# io-pack-2-1.net
KiCad netlist of a schematic drawn in EAGLE
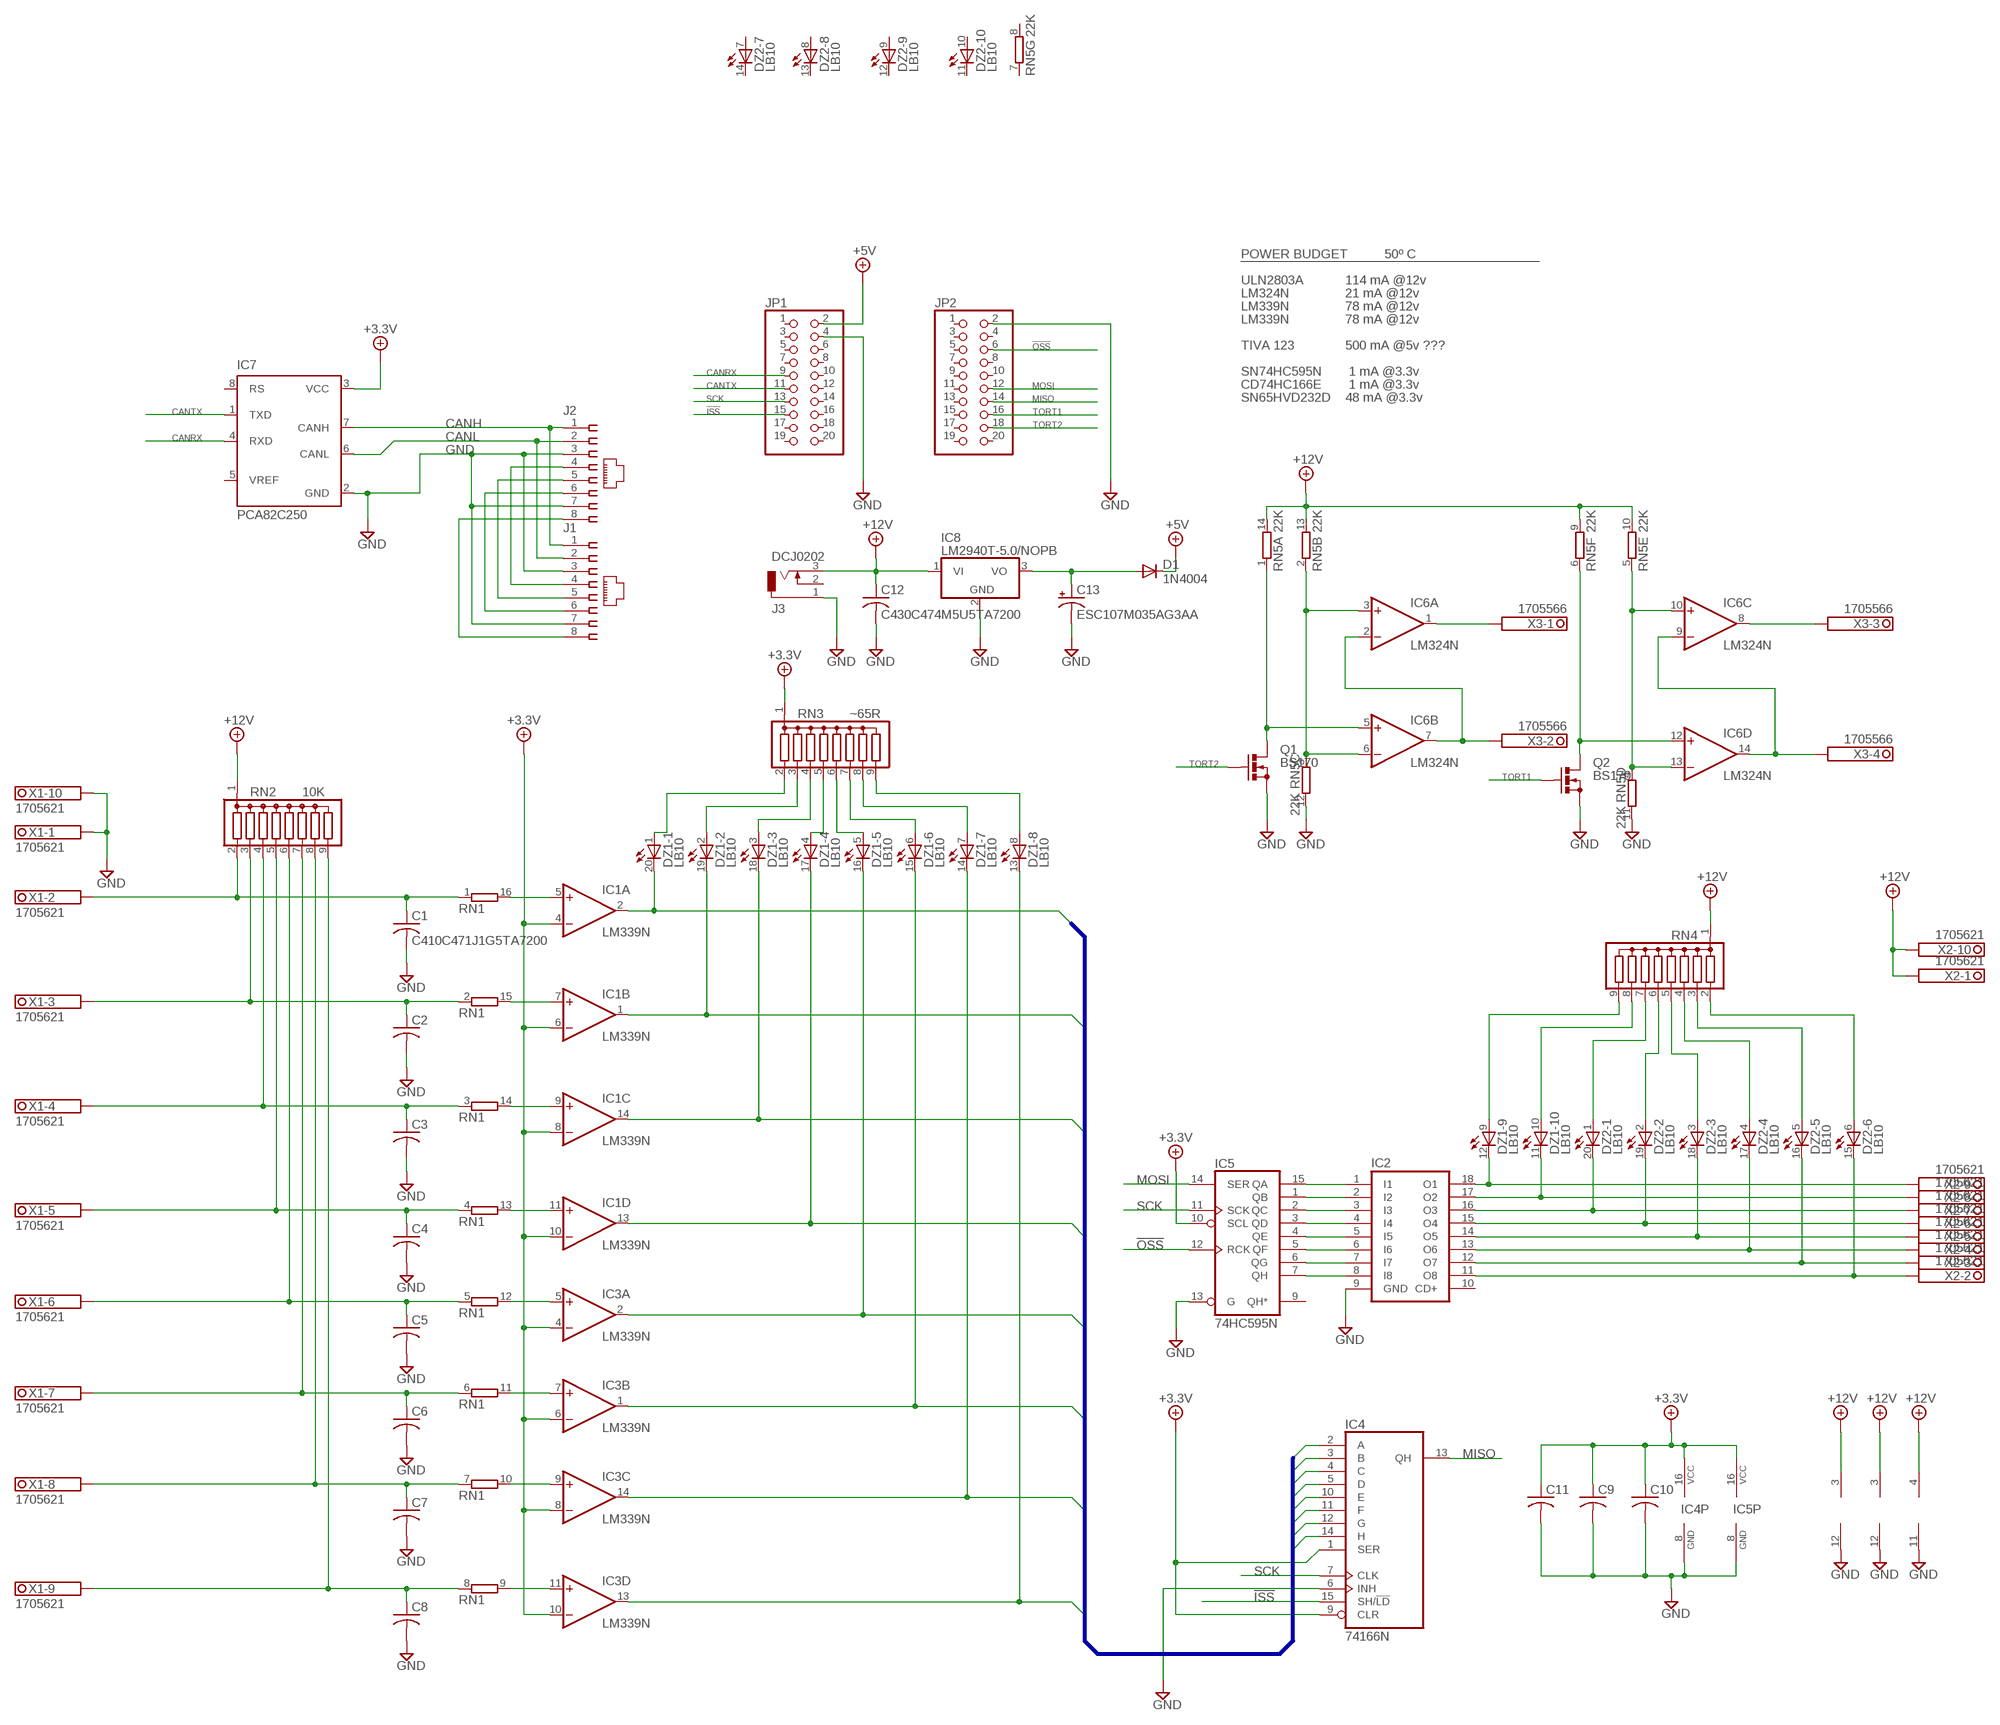
[diagram p0: schematic, sheet 1]

(export (version "E")
  (design (tool "Eeschema 10.0.6"))
  (components
    (comp (ref "C1")
      (value "C410C471J1G5TA7200")
      (footprint "eagle-import:C050-025X075")
      (libsource (lib "eagle-import") (part "C-US050-025X075"))
    )
    (comp (ref "C2")
      (value "C-US050-025X075")
      (footprint "eagle-import:C050-025X075")
      (libsource (lib "eagle-import") (part "C-US050-025X075"))
    )
    (comp (ref "C3")
      (value "C-US050-025X075")
      (footprint "eagle-import:C050-025X075")
      (libsource (lib "eagle-import") (part "C-US050-025X075"))
    )
    (comp (ref "C4")
      (value "C-US050-025X075")
      (footprint "eagle-import:C050-025X075")
      (libsource (lib "eagle-import") (part "C-US050-025X075"))
    )
    (comp (ref "C5")
      (value "C-US050-025X075")
      (footprint "eagle-import:C050-025X075")
      (libsource (lib "eagle-import") (part "C-US050-025X075"))
    )
    (comp (ref "C6")
      (value "C-US050-025X075")
      (footprint "eagle-import:C050-025X075")
      (libsource (lib "eagle-import") (part "C-US050-025X075"))
    )
    (comp (ref "C7")
      (value "C-US050-025X075")
      (footprint "eagle-import:C050-025X075")
      (libsource (lib "eagle-import") (part "C-US050-025X075"))
    )
    (comp (ref "C8")
      (value "C-US050-025X075")
      (footprint "eagle-import:C050-025X075")
      (libsource (lib "eagle-import") (part "C-US050-025X075"))
    )
    (comp (ref "C9")
      (value "C-US050-025X075")
      (footprint "eagle-import:C050-025X075")
      (libsource (lib "eagle-import") (part "C-US050-025X075"))
    )
    (comp (ref "C10")
      (value "C-US050-025X075")
      (footprint "eagle-import:C050-025X075")
      (libsource (lib "eagle-import") (part "C-US050-025X075"))
    )
    (comp (ref "C11")
      (value "C-US050-025X075")
      (footprint "eagle-import:C050-025X075")
      (libsource (lib "eagle-import") (part "C-US050-025X075"))
    )
    (comp (ref "C12")
      (value "C430C474M5U5TA7200")
      (footprint "eagle-import:C075-032X103")
      (libsource (lib "eagle-import") (part "C-US075-032X103"))
    )
    (comp (ref "C13")
      (value "ESC107M035AG3AA")
      (footprint "eagle-import:E3,5-8")
      (libsource (lib "eagle-import") (part "CPOL-USE3.5-8"))
    )
    (comp (ref "D1")
      (value "1N4004")
      (footprint "eagle-import:DO41-10")
      (libsource (lib "eagle-import") (part "1N4004"))
    )
    (comp (ref "DZ1")
      (value "LB10")
      (footprint "eagle-import:LB10")
      (libsource (lib "eagle-import") (part "LB10"))
    )
    (comp (ref "DZ2")
      (value "LB10")
      (footprint "eagle-import:LB10")
      (libsource (lib "eagle-import") (part "LB10"))
    )
    (comp (ref "IC1")
      (value "LM339N")
      (footprint "eagle-import:DIL14")
      (libsource (lib "eagle-import") (part "LM339N"))
    )
    (comp (ref "IC2")
      (value "ULN2803A")
      (footprint "eagle-import:DIL18")
      (libsource (lib "eagle-import") (part "ULN2803A"))
    )
    (comp (ref "IC3")
      (value "LM339N")
      (footprint "eagle-import:DIL14")
      (libsource (lib "eagle-import") (part "LM339N"))
    )
    (comp (ref "IC4")
      (value "74166N")
      (footprint "eagle-import:DIL16")
      (libsource (lib "eagle-import") (part "74166N"))
    )
    (comp (ref "IC5")
      (value "74HC595N")
      (footprint "eagle-import:DIL16")
      (libsource (lib "eagle-import") (part "74595NLS"))
    )
    (comp (ref "IC6")
      (value "LM324N")
      (footprint "eagle-import:DIL14")
      (libsource (lib "eagle-import") (part "LM324N"))
    )
    (comp (ref "IC7")
      (value "PCA82C250")
      (footprint "eagle-import:DIL08")
      (libsource (lib "eagle-import") (part "PCA82C250"))
    )
    (comp (ref "IC8")
      (value "LM2940T-5.0/NOPB")
      (footprint "eagle-import:TO220V")
      (libsource (lib "eagle-import") (part "78TV05"))
    )
    (comp (ref "J1")
      (value "555164-1")
      (footprint "eagle-import:555164-1")
      (libsource (lib "eagle-import") (part "555164-1"))
    )
    (comp (ref "J2")
      (value "555164-1")
      (footprint "eagle-import:555164-1")
      (libsource (lib "eagle-import") (part "555164-1"))
    )
    (comp (ref "J3")
      (value "DCJ0202")
      (footprint "eagle-import:DCJ0202")
      (libsource (lib "eagle-import") (part "DCJ0202"))
    )
    (comp (ref "JP1")
      (value "PINHD-2X10")
      (footprint "eagle-import:2X10")
      (libsource (lib "eagle-import") (part "PINHD-2X10"))
    )
    (comp (ref "JP2")
      (value "PINHD-2X10")
      (footprint "eagle-import:2X10")
      (libsource (lib "eagle-import") (part "PINHD-2X10"))
    )
    (comp (ref "Q1")
      (value "BS170")
      (footprint "eagle-import:SOT54E")
      (libsource (lib "eagle-import") (part "BS170"))
    )
    (comp (ref "Q2")
      (value "BS170")
      (footprint "eagle-import:SOT54E")
      (libsource (lib "eagle-import") (part "BS170"))
    )
    (comp (ref "RN1")
      (value "8R-P")
      (footprint "eagle-import:DIL16")
      (libsource (lib "eagle-import") (part "8R-P"))
    )
    (comp (ref "RN2")
      (value "10K")
      (footprint "eagle-import:SIL9")
      (libsource (lib "eagle-import") (part "G08R"))
    )
    (comp (ref "RN3")
      (value "~65R")
      (footprint "eagle-import:SIL9")
      (libsource (lib "eagle-import") (part "G08R"))
    )
    (comp (ref "RN4")
      (value "G08R")
      (footprint "eagle-import:SIL9")
      (libsource (lib "eagle-import") (part "G08R"))
    )
    (comp (ref "RN5")
      (value "22K")
      (footprint "eagle-import:DIL14")
      (libsource (lib "eagle-import") (part "7R-N"))
    )
    (comp (ref "X1")
      (value "1705621")
      (footprint "eagle-import:1705621")
      (libsource (lib "eagle-import") (part "1705621"))
    )
    (comp (ref "X2")
      (value "1705621")
      (footprint "eagle-import:1705621")
      (libsource (lib "eagle-import") (part "1705621"))
    )
    (comp (ref "X3")
      (value "1705566")
      (footprint "eagle-import:1705566")
      (libsource (lib "eagle-import") (part "1705566"))
    )
  )
  (nets
    (net (code "1") (name "+3.3V") (class "Default")
      (node (ref "C10") (pin "1") (pinfunction "1_1") (pintype "passive"))
      (node (ref "C11") (pin "1") (pinfunction "1_1") (pintype "passive"))
      (node (ref "C9") (pin "1") (pinfunction "1_1") (pintype "passive"))
      (node (ref "IC1") (pin "10") (pinfunction "-IN_10") (pintype "input"))
      (node (ref "IC1") (pin "4") (pinfunction "-IN_4") (pintype "input"))
      (node (ref "IC1") (pin "6") (pinfunction "-IN_6") (pintype "input"))
      (node (ref "IC1") (pin "8") (pinfunction "-IN_8") (pintype "input"))
      (node (ref "IC3") (pin "10") (pinfunction "-IN_10") (pintype "input"))
      (node (ref "IC3") (pin "4") (pinfunction "-IN_4") (pintype "input"))
      (node (ref "IC3") (pin "6") (pinfunction "-IN_6") (pintype "input"))
      (node (ref "IC3") (pin "8") (pinfunction "-IN_8") (pintype "input"))
      (node (ref "IC4") (pin "1") (pinfunction "SER_1") (pintype "input"))
      (node (ref "IC4") (pin "16") (pinfunction "VCC_16") (pintype "power_in"))
      (node (ref "IC4") (pin "9") (pinfunction "CLR_9") (pintype "input"))
      (node (ref "IC5") (pin "10") (pinfunction "SCL_10") (pintype "input"))
      (node (ref "IC5") (pin "16") (pinfunction "VCC_16") (pintype "power_in"))
      (node (ref "IC7") (pin "3") (pinfunction "VCC_3") (pintype "power_in"))
      (node (ref "RN3") (pin "1") (pinfunction "1_1") (pintype "passive"))
    )
    (net (code "2") (name "+5V") (class "Default")
      (node (ref "D1") (pin "C") (pinfunction "C_C") (pintype "passive"))
      (node (ref "JP1") (pin "2") (pinfunction "2_2") (pintype "passive"))
    )
    (net (code "3") (name "+12V") (class "Default")
      (node (ref "C12") (pin "1") (pinfunction "1_1") (pintype "passive"))
      (node (ref "IC1") (pin "3") (pinfunction "V+_3") (pintype "power_in"))
      (node (ref "IC3") (pin "3") (pinfunction "V+_3") (pintype "power_in"))
      (node (ref "IC6") (pin "4") (pinfunction "V+_4") (pintype "power_in"))
      (node (ref "IC8") (pin "1") (pinfunction "VI_1") (pintype "input"))
      (node (ref "J3") (pin "3") (pinfunction "3_3") (pintype "passive"))
      (node (ref "RN2") (pin "1") (pinfunction "1_1") (pintype "passive"))
      (node (ref "RN4") (pin "1") (pinfunction "1_1") (pintype "passive"))
      (node (ref "RN5") (pin "10") (pinfunction "2_10") (pintype "passive"))
      (node (ref "RN5") (pin "13") (pinfunction "2_13") (pintype "passive"))
      (node (ref "RN5") (pin "14") (pinfunction "2_14") (pintype "passive"))
      (node (ref "RN5") (pin "9") (pinfunction "2_9") (pintype "passive"))
      (node (ref "X2") (pin "1.1") (pinfunction "1A_1.1") (pintype "passive"))
      (node (ref "X2") (pin "1.2") (pinfunction "1A_1.2") (pintype "passive"))
      (node (ref "X2") (pin "10.1") (pinfunction "1A_10.1") (pintype "passive"))
      (node (ref "X2") (pin "10.2") (pinfunction "1A_10.2") (pintype "passive"))
    )
    (net (code "4") (name "/CANH") (class "Default")
      (node (ref "IC7") (pin "7") (pinfunction "CANH_7") (pintype "bidirectional"))
      (node (ref "J1") (pin "1") (pinfunction "1_1") (pintype "passive"))
      (node (ref "J2") (pin "1") (pinfunction "1_1") (pintype "passive"))
    )
    (net (code "5") (name "/CANL") (class "Default")
      (node (ref "IC7") (pin "6") (pinfunction "CANL_6") (pintype "bidirectional"))
      (node (ref "J1") (pin "2") (pinfunction "2_2") (pintype "passive"))
      (node (ref "J2") (pin "2") (pinfunction "2_2") (pintype "passive"))
    )
    (net (code "6") (name "/CANRX") (class "Default")
      (node (ref "IC7") (pin "4") (pinfunction "RXD_4") (pintype "output"))
      (node (ref "JP1") (pin "9") (pinfunction "9_9") (pintype "passive"))
    )
    (net (code "7") (name "/CANTX") (class "Default")
      (node (ref "IC7") (pin "1") (pinfunction "TXD_1") (pintype "input"))
      (node (ref "JP1") (pin "11") (pinfunction "11_11") (pintype "passive"))
    )
    (net (code "8") (name "/IN0") (class "Default")
      (node (ref "DZ1") (pin "20") (pinfunction "C_20") (pintype "passive"))
      (node (ref "IC1") (pin "2") (pinfunction "OUT_2") (pintype "open_collector"))
      (node (ref "IC4") (pin "2") (pinfunction "A_2") (pintype "input"))
    )
    (net (code "9") (name "/IN1") (class "Default")
      (node (ref "DZ1") (pin "19") (pinfunction "C_19") (pintype "passive"))
      (node (ref "IC1") (pin "1") (pinfunction "OUT_1") (pintype "open_collector"))
      (node (ref "IC4") (pin "3") (pinfunction "B_3") (pintype "input"))
    )
    (net (code "10") (name "/IN2") (class "Default")
      (node (ref "DZ1") (pin "18") (pinfunction "C_18") (pintype "passive"))
      (node (ref "IC1") (pin "14") (pinfunction "OUT_14") (pintype "open_collector"))
      (node (ref "IC4") (pin "4") (pinfunction "C_4") (pintype "input"))
    )
    (net (code "11") (name "/IN3") (class "Default")
      (node (ref "DZ1") (pin "17") (pinfunction "C_17") (pintype "passive"))
      (node (ref "IC1") (pin "13") (pinfunction "OUT_13") (pintype "open_collector"))
      (node (ref "IC4") (pin "5") (pinfunction "D_5") (pintype "input"))
    )
    (net (code "12") (name "/IN4") (class "Default")
      (node (ref "DZ1") (pin "16") (pinfunction "C_16") (pintype "passive"))
      (node (ref "IC3") (pin "2") (pinfunction "OUT_2") (pintype "open_collector"))
      (node (ref "IC4") (pin "10") (pinfunction "E_10") (pintype "input"))
    )
    (net (code "13") (name "/IN5") (class "Default")
      (node (ref "DZ1") (pin "15") (pinfunction "C_15") (pintype "passive"))
      (node (ref "IC3") (pin "1") (pinfunction "OUT_1") (pintype "open_collector"))
      (node (ref "IC4") (pin "11") (pinfunction "F_11") (pintype "input"))
    )
    (net (code "14") (name "/IN6") (class "Default")
      (node (ref "DZ1") (pin "14") (pinfunction "C_14") (pintype "passive"))
      (node (ref "IC3") (pin "14") (pinfunction "OUT_14") (pintype "open_collector"))
      (node (ref "IC4") (pin "12") (pinfunction "G_12") (pintype "input"))
    )
    (net (code "15") (name "/IN7") (class "Default")
      (node (ref "DZ1") (pin "13") (pinfunction "C_13") (pintype "passive"))
      (node (ref "IC3") (pin "13") (pinfunction "OUT_13") (pintype "open_collector"))
      (node (ref "IC4") (pin "14") (pinfunction "H_14") (pintype "input"))
    )
    (net (code "16") (name "/MISO") (class "Default")
      (node (ref "IC4") (pin "13") (pinfunction "QH_13") (pintype "output"))
      (node (ref "JP2") (pin "14") (pinfunction "14_14") (pintype "passive"))
    )
    (net (code "17") (name "/MOSI") (class "Default")
      (node (ref "IC5") (pin "14") (pinfunction "SER_14") (pintype "input"))
      (node (ref "JP2") (pin "12") (pinfunction "12_12") (pintype "passive"))
    )
    (net (code "18") (name "/SCK") (class "Default")
      (node (ref "IC4") (pin "7") (pinfunction "CLK_7") (pintype "input"))
      (node (ref "IC5") (pin "11") (pinfunction "SCK_11") (pintype "input"))
      (node (ref "JP1") (pin "13") (pinfunction "13_13") (pintype "passive"))
    )
    (net (code "19") (name "/TORT1") (class "Default")
      (node (ref "JP2") (pin "16") (pinfunction "16_16") (pintype "passive"))
      (node (ref "Q2") (pin "G") (pinfunction "G_G") (pintype "passive"))
    )
    (net (code "20") (name "/TORT2") (class "Default")
      (node (ref "JP2") (pin "18") (pinfunction "18_18") (pintype "passive"))
      (node (ref "Q1") (pin "G") (pinfunction "G_G") (pintype "passive"))
    )
    (net (code "21") (name "/~{ISS}") (class "Default")
      (node (ref "IC4") (pin "15") (pinfunction "SH/~{LD}_15") (pintype "input"))
      (node (ref "JP1") (pin "15") (pinfunction "15_15") (pintype "passive"))
    )
    (net (code "22") (name "/~{OSS}") (class "Default")
      (node (ref "IC5") (pin "12") (pinfunction "RCK_12") (pintype "input"))
      (node (ref "JP2") (pin "6") (pinfunction "6_6") (pintype "passive"))
    )
    (net (code "23") (name "GND") (class "Default")
      (node (ref "C1") (pin "2") (pinfunction "2_2") (pintype "passive"))
      (node (ref "C10") (pin "2") (pinfunction "2_2") (pintype "passive"))
      (node (ref "C11") (pin "2") (pinfunction "2_2") (pintype "passive"))
      (node (ref "C12") (pin "2") (pinfunction "2_2") (pintype "passive"))
      (node (ref "C13") (pin "-") (pinfunction "-_-") (pintype "passive"))
      (node (ref "C2") (pin "2") (pinfunction "2_2") (pintype "passive"))
      (node (ref "C3") (pin "2") (pinfunction "2_2") (pintype "passive"))
      (node (ref "C4") (pin "2") (pinfunction "2_2") (pintype "passive"))
      (node (ref "C5") (pin "2") (pinfunction "2_2") (pintype "passive"))
      (node (ref "C6") (pin "2") (pinfunction "2_2") (pintype "passive"))
      (node (ref "C7") (pin "2") (pinfunction "2_2") (pintype "passive"))
      (node (ref "C8") (pin "2") (pinfunction "2_2") (pintype "passive"))
      (node (ref "C9") (pin "2") (pinfunction "2_2") (pintype "passive"))
      (node (ref "IC1") (pin "12") (pinfunction "GND_12") (pintype "power_in"))
      (node (ref "IC2") (pin "9") (pinfunction "GND_9") (pintype "power_in"))
      (node (ref "IC3") (pin "12") (pinfunction "GND_12") (pintype "power_in"))
      (node (ref "IC4") (pin "6") (pinfunction "INH_6") (pintype "input"))
      (node (ref "IC4") (pin "8") (pinfunction "GND_8") (pintype "power_in"))
      (node (ref "IC5") (pin "13") (pinfunction "G_13") (pintype "input"))
      (node (ref "IC5") (pin "8") (pinfunction "GND_8") (pintype "power_in"))
      (node (ref "IC6") (pin "11") (pinfunction "V-_11") (pintype "power_in"))
      (node (ref "IC7") (pin "2") (pinfunction "GND_2") (pintype "power_in"))
      (node (ref "IC8") (pin "2") (pinfunction "GND_2") (pintype "passive"))
      (node (ref "J1") (pin "3") (pinfunction "3_3") (pintype "passive"))
      (node (ref "J1") (pin "7") (pinfunction "7_7") (pintype "passive"))
      (node (ref "J2") (pin "3") (pinfunction "3_3") (pintype "passive"))
      (node (ref "J2") (pin "7") (pinfunction "7_7") (pintype "passive"))
      (node (ref "J3") (pin "1") (pinfunction "1_1") (pintype "passive"))
      (node (ref "JP1") (pin "4") (pinfunction "4_4") (pintype "passive"))
      (node (ref "JP2") (pin "2") (pinfunction "2_2") (pintype "passive"))
      (node (ref "Q1") (pin "S") (pinfunction "S_S") (pintype "passive"))
      (node (ref "Q2") (pin "S") (pinfunction "S_S") (pintype "passive"))
      (node (ref "RN5") (pin "11") (pinfunction "2_11") (pintype "passive"))
      (node (ref "RN5") (pin "12") (pinfunction "2_12") (pintype "passive"))
      (node (ref "X1") (pin "1.1") (pinfunction "1A_1.1") (pintype "passive"))
      (node (ref "X1") (pin "1.2") (pinfunction "1A_1.2") (pintype "passive"))
      (node (ref "X1") (pin "10.1") (pinfunction "1A_10.1") (pintype "passive"))
      (node (ref "X1") (pin "10.2") (pinfunction "1A_10.2") (pintype "passive"))
    )
    (net (code "24") (name "Net-(C1-Pad1)") (class "Default")
      (node (ref "C1") (pin "1") (pinfunction "1_1") (pintype "passive"))
      (node (ref "RN1") (pin "1") (pinfunction "1_1") (pintype "passive"))
      (node (ref "RN2") (pin "2") (pinfunction "2_2") (pintype "passive"))
      (node (ref "X1") (pin "2.1") (pinfunction "1A_2.1") (pintype "passive"))
      (node (ref "X1") (pin "2.2") (pinfunction "1A_2.2") (pintype "passive"))
    )
    (net (code "25") (name "Net-(DZ1A-A)") (class "Default")
      (node (ref "DZ1") (pin "1") (pinfunction "A_1") (pintype "passive"))
      (node (ref "RN3") (pin "2") (pinfunction "2_2") (pintype "passive"))
    )
    (net (code "26") (name "Net-(DZ1B-A)") (class "Default")
      (node (ref "DZ1") (pin "10") (pinfunction "A_10") (pintype "passive"))
      (node (ref "RN4") (pin "8") (pinfunction "8_8") (pintype "passive"))
    )
    (net (code "27") (name "Net-(DZ1B-C)") (class "Default")
      (node (ref "DZ1") (pin "11") (pinfunction "C_11") (pintype "passive"))
      (node (ref "IC2") (pin "17") (pinfunction "O2_17") (pintype "open_collector"))
      (node (ref "X2") (pin "8.1") (pinfunction "1A_8.1") (pintype "passive"))
      (node (ref "X2") (pin "8.2") (pinfunction "1A_8.2") (pintype "passive"))
    )
    (net (code "28") (name "Net-(DZ1C-A)") (class "Default")
      (node (ref "DZ1") (pin "2") (pinfunction "A_2") (pintype "passive"))
      (node (ref "RN3") (pin "3") (pinfunction "3_3") (pintype "passive"))
    )
    (net (code "29") (name "Net-(DZ1D-A)") (class "Default")
      (node (ref "DZ1") (pin "3") (pinfunction "A_3") (pintype "passive"))
      (node (ref "RN3") (pin "4") (pinfunction "4_4") (pintype "passive"))
    )
    (net (code "30") (name "Net-(DZ1E-A)") (class "Default")
      (node (ref "DZ1") (pin "4") (pinfunction "A_4") (pintype "passive"))
      (node (ref "RN3") (pin "5") (pinfunction "5_5") (pintype "passive"))
    )
    (net (code "31") (name "Net-(DZ1F-A)") (class "Default")
      (node (ref "DZ1") (pin "5") (pinfunction "A_5") (pintype "passive"))
      (node (ref "RN3") (pin "6") (pinfunction "6_6") (pintype "passive"))
    )
    (net (code "32") (name "Net-(DZ1G-A)") (class "Default")
      (node (ref "DZ1") (pin "6") (pinfunction "A_6") (pintype "passive"))
      (node (ref "RN3") (pin "7") (pinfunction "7_7") (pintype "passive"))
    )
    (net (code "33") (name "Net-(DZ1H-A)") (class "Default")
      (node (ref "DZ1") (pin "7") (pinfunction "A_7") (pintype "passive"))
      (node (ref "RN3") (pin "8") (pinfunction "8_8") (pintype "passive"))
    )
    (net (code "34") (name "Net-(DZ1I-A)") (class "Default")
      (node (ref "DZ1") (pin "8") (pinfunction "A_8") (pintype "passive"))
      (node (ref "RN3") (pin "9") (pinfunction "9_9") (pintype "passive"))
    )
    (net (code "35") (name "Net-(DZ1J-A)") (class "Default")
      (node (ref "DZ1") (pin "9") (pinfunction "A_9") (pintype "passive"))
      (node (ref "RN4") (pin "9") (pinfunction "9_9") (pintype "passive"))
    )
    (net (code "36") (name "Net-(DZ1J-C)") (class "Default")
      (node (ref "DZ1") (pin "12") (pinfunction "C_12") (pintype "passive"))
      (node (ref "IC2") (pin "18") (pinfunction "O1_18") (pintype "open_collector"))
      (node (ref "X2") (pin "9.1") (pinfunction "1A_9.1") (pintype "passive"))
      (node (ref "X2") (pin "9.2") (pinfunction "1A_9.2") (pintype "passive"))
    )
    (net (code "37") (name "Net-(DZ2A-A)") (class "Default")
      (node (ref "DZ2") (pin "1") (pinfunction "A_1") (pintype "passive"))
      (node (ref "RN4") (pin "7") (pinfunction "7_7") (pintype "passive"))
    )
    (net (code "38") (name "Net-(DZ2A-C)") (class "Default")
      (node (ref "DZ2") (pin "20") (pinfunction "C_20") (pintype "passive"))
      (node (ref "IC2") (pin "16") (pinfunction "O3_16") (pintype "open_collector"))
      (node (ref "X2") (pin "7.1") (pinfunction "1A_7.1") (pintype "passive"))
      (node (ref "X2") (pin "7.2") (pinfunction "1A_7.2") (pintype "passive"))
    )
    (net (code "39") (name "Net-(DZ2C-A)") (class "Default")
      (node (ref "DZ2") (pin "2") (pinfunction "A_2") (pintype "passive"))
      (node (ref "RN4") (pin "6") (pinfunction "6_6") (pintype "passive"))
    )
    (net (code "40") (name "Net-(DZ2C-C)") (class "Default")
      (node (ref "DZ2") (pin "19") (pinfunction "C_19") (pintype "passive"))
      (node (ref "IC2") (pin "15") (pinfunction "O4_15") (pintype "open_collector"))
      (node (ref "X2") (pin "6.1") (pinfunction "1A_6.1") (pintype "passive"))
      (node (ref "X2") (pin "6.2") (pinfunction "1A_6.2") (pintype "passive"))
    )
    (net (code "41") (name "Net-(DZ2D-A)") (class "Default")
      (node (ref "DZ2") (pin "3") (pinfunction "A_3") (pintype "passive"))
      (node (ref "RN4") (pin "5") (pinfunction "5_5") (pintype "passive"))
    )
    (net (code "42") (name "Net-(DZ2D-C)") (class "Default")
      (node (ref "DZ2") (pin "18") (pinfunction "C_18") (pintype "passive"))
      (node (ref "IC2") (pin "14") (pinfunction "O5_14") (pintype "open_collector"))
      (node (ref "X2") (pin "5.1") (pinfunction "1A_5.1") (pintype "passive"))
      (node (ref "X2") (pin "5.2") (pinfunction "1A_5.2") (pintype "passive"))
    )
    (net (code "43") (name "Net-(DZ2E-A)") (class "Default")
      (node (ref "DZ2") (pin "4") (pinfunction "A_4") (pintype "passive"))
      (node (ref "RN4") (pin "4") (pinfunction "4_4") (pintype "passive"))
    )
    (net (code "44") (name "Net-(DZ2E-C)") (class "Default")
      (node (ref "DZ2") (pin "17") (pinfunction "C_17") (pintype "passive"))
      (node (ref "IC2") (pin "13") (pinfunction "O6_13") (pintype "open_collector"))
      (node (ref "X2") (pin "4.1") (pinfunction "1A_4.1") (pintype "passive"))
      (node (ref "X2") (pin "4.2") (pinfunction "1A_4.2") (pintype "passive"))
    )
    (net (code "45") (name "Net-(DZ2F-A)") (class "Default")
      (node (ref "DZ2") (pin "5") (pinfunction "A_5") (pintype "passive"))
      (node (ref "RN4") (pin "3") (pinfunction "3_3") (pintype "passive"))
    )
    (net (code "46") (name "Net-(DZ2F-C)") (class "Default")
      (node (ref "DZ2") (pin "16") (pinfunction "C_16") (pintype "passive"))
      (node (ref "IC2") (pin "12") (pinfunction "O7_12") (pintype "open_collector"))
      (node (ref "X2") (pin "3.1") (pinfunction "1A_3.1") (pintype "passive"))
      (node (ref "X2") (pin "3.2") (pinfunction "1A_3.2") (pintype "passive"))
    )
    (net (code "47") (name "Net-(DZ2G-A)") (class "Default")
      (node (ref "DZ2") (pin "6") (pinfunction "A_6") (pintype "passive"))
      (node (ref "RN4") (pin "2") (pinfunction "2_2") (pintype "passive"))
    )
    (net (code "48") (name "Net-(DZ2G-C)") (class "Default")
      (node (ref "DZ2") (pin "15") (pinfunction "C_15") (pintype "passive"))
      (node (ref "IC2") (pin "11") (pinfunction "O8_11") (pintype "open_collector"))
      (node (ref "X2") (pin "2.1") (pinfunction "1A_2.1") (pintype "passive"))
      (node (ref "X2") (pin "2.2") (pinfunction "1A_2.2") (pintype "passive"))
    )
    (net (code "49") (name "Net-(IC1A-+IN)") (class "Default")
      (node (ref "IC1") (pin "5") (pinfunction "+IN_5") (pintype "input"))
      (node (ref "RN1") (pin "16") (pinfunction "2_16") (pintype "passive"))
    )
    (net (code "50") (name "Net-(IC1B-+IN)") (class "Default")
      (node (ref "IC1") (pin "7") (pinfunction "+IN_7") (pintype "input"))
      (node (ref "RN1") (pin "15") (pinfunction "2_15") (pintype "passive"))
    )
    (net (code "51") (name "Net-(IC1C-+IN)") (class "Default")
      (node (ref "IC1") (pin "9") (pinfunction "+IN_9") (pintype "input"))
      (node (ref "RN1") (pin "14") (pinfunction "2_14") (pintype "passive"))
    )
    (net (code "52") (name "Net-(IC1D-+IN)") (class "Default")
      (node (ref "IC1") (pin "11") (pinfunction "+IN_11") (pintype "input"))
      (node (ref "RN1") (pin "13") (pinfunction "2_13") (pintype "passive"))
    )
    (net (code "53") (name "Net-(IC2-I1)") (class "Default")
      (node (ref "IC2") (pin "1") (pinfunction "I1_1") (pintype "input"))
      (node (ref "IC5") (pin "15") (pinfunction "QA_15") (pintype "tri_state"))
    )
    (net (code "54") (name "Net-(IC2-I2)") (class "Default")
      (node (ref "IC2") (pin "2") (pinfunction "I2_2") (pintype "input"))
      (node (ref "IC5") (pin "1") (pinfunction "QB_1") (pintype "tri_state"))
    )
    (net (code "55") (name "Net-(IC2-I3)") (class "Default")
      (node (ref "IC2") (pin "3") (pinfunction "I3_3") (pintype "input"))
      (node (ref "IC5") (pin "2") (pinfunction "QC_2") (pintype "tri_state"))
    )
    (net (code "56") (name "Net-(IC2-I4)") (class "Default")
      (node (ref "IC2") (pin "4") (pinfunction "I4_4") (pintype "input"))
      (node (ref "IC5") (pin "3") (pinfunction "QD_3") (pintype "tri_state"))
    )
    (net (code "57") (name "Net-(IC2-I5)") (class "Default")
      (node (ref "IC2") (pin "5") (pinfunction "I5_5") (pintype "input"))
      (node (ref "IC5") (pin "4") (pinfunction "QE_4") (pintype "tri_state"))
    )
    (net (code "58") (name "Net-(IC2-I6)") (class "Default")
      (node (ref "IC2") (pin "6") (pinfunction "I6_6") (pintype "input"))
      (node (ref "IC5") (pin "5") (pinfunction "QF_5") (pintype "tri_state"))
    )
    (net (code "59") (name "Net-(IC2-I7)") (class "Default")
      (node (ref "IC2") (pin "7") (pinfunction "I7_7") (pintype "input"))
      (node (ref "IC5") (pin "6") (pinfunction "QG_6") (pintype "tri_state"))
    )
    (net (code "60") (name "Net-(IC2-I8)") (class "Default")
      (node (ref "IC2") (pin "8") (pinfunction "I8_8") (pintype "input"))
      (node (ref "IC5") (pin "7") (pinfunction "QH_7") (pintype "tri_state"))
    )
    (net (code "61") (name "Net-(IC3A-+IN)") (class "Default")
      (node (ref "IC3") (pin "5") (pinfunction "+IN_5") (pintype "input"))
      (node (ref "RN1") (pin "12") (pinfunction "2_12") (pintype "passive"))
    )
    (net (code "62") (name "Net-(IC3B-+IN)") (class "Default")
      (node (ref "IC3") (pin "7") (pinfunction "+IN_7") (pintype "input"))
      (node (ref "RN1") (pin "11") (pinfunction "2_11") (pintype "passive"))
    )
    (net (code "63") (name "Net-(IC3C-+IN)") (class "Default")
      (node (ref "IC3") (pin "9") (pinfunction "+IN_9") (pintype "input"))
      (node (ref "RN1") (pin "10") (pinfunction "2_10") (pintype "passive"))
    )
    (net (code "64") (name "Net-(IC3D-+IN)") (class "Default")
      (node (ref "IC3") (pin "11") (pinfunction "+IN_11") (pintype "input"))
      (node (ref "RN1") (pin "9") (pinfunction "2_9") (pintype "passive"))
    )
    (net (code "65") (name "Net-(IC6A-+IN)") (class "Default")
      (node (ref "IC6") (pin "3") (pinfunction "+IN_3") (pintype "input"))
      (node (ref "IC6") (pin "6") (pinfunction "-IN_6") (pintype "input"))
      (node (ref "RN5") (pin "2") (pinfunction "1_2") (pintype "passive"))
      (node (ref "RN5") (pin "3") (pinfunction "1_3") (pintype "passive"))
    )
    (net (code "66") (name "Net-(IC6A--IN)") (class "Default")
      (node (ref "IC6") (pin "2") (pinfunction "-IN_2") (pintype "input"))
      (node (ref "IC6") (pin "7") (pinfunction "OUT_7") (pintype "output"))
      (node (ref "X3") (pin "2.1") (pinfunction "1A_2.1") (pintype "passive"))
      (node (ref "X3") (pin "2.2") (pinfunction "1A_2.2") (pintype "passive"))
    )
    (net (code "67") (name "Net-(IC6A-OUT)") (class "Default")
      (node (ref "IC6") (pin "1") (pinfunction "OUT_1") (pintype "output"))
      (node (ref "X3") (pin "1.1") (pinfunction "1A_1.1") (pintype "passive"))
      (node (ref "X3") (pin "1.2") (pinfunction "1A_1.2") (pintype "passive"))
    )
    (net (code "68") (name "Net-(IC6B-+IN)") (class "Default")
      (node (ref "IC6") (pin "5") (pinfunction "+IN_5") (pintype "input"))
      (node (ref "Q1") (pin "D") (pinfunction "D_D") (pintype "passive"))
      (node (ref "RN5") (pin "1") (pinfunction "1_1") (pintype "passive"))
    )
    (net (code "69") (name "Net-(IC6C-+IN)") (class "Default")
      (node (ref "IC6") (pin "10") (pinfunction "+IN_10") (pintype "input"))
      (node (ref "IC6") (pin "13") (pinfunction "-IN_13") (pintype "input"))
      (node (ref "RN5") (pin "4") (pinfunction "1_4") (pintype "passive"))
      (node (ref "RN5") (pin "5") (pinfunction "1_5") (pintype "passive"))
    )
    (net (code "70") (name "Net-(IC6C--IN)") (class "Default")
      (node (ref "IC6") (pin "14") (pinfunction "OUT_14") (pintype "output"))
      (node (ref "IC6") (pin "9") (pinfunction "-IN_9") (pintype "input"))
      (node (ref "X3") (pin "4.1") (pinfunction "1A_4.1") (pintype "passive"))
      (node (ref "X3") (pin "4.2") (pinfunction "1A_4.2") (pintype "passive"))
    )
    (net (code "71") (name "Net-(IC6C-OUT)") (class "Default")
      (node (ref "IC6") (pin "8") (pinfunction "OUT_8") (pintype "output"))
      (node (ref "X3") (pin "3.1") (pinfunction "1A_3.1") (pintype "passive"))
      (node (ref "X3") (pin "3.2") (pinfunction "1A_3.2") (pintype "passive"))
    )
    (net (code "72") (name "Net-(IC6D-+IN)") (class "Default")
      (node (ref "IC6") (pin "12") (pinfunction "+IN_12") (pintype "input"))
      (node (ref "Q2") (pin "D") (pinfunction "D_D") (pintype "passive"))
      (node (ref "RN5") (pin "6") (pinfunction "1_6") (pintype "passive"))
    )
    (net (code "73") (name "Net-(IC8-VO)") (class "Default")
      (node (ref "C13") (pin "+") (pinfunction "+_+") (pintype "passive"))
      (node (ref "D1") (pin "A") (pinfunction "A_A") (pintype "passive"))
      (node (ref "IC8") (pin "3") (pinfunction "VO_3") (pintype "passive"))
    )
    (net (code "74") (name "Net-(J1-Pad4)") (class "Default")
      (node (ref "J1") (pin "4") (pinfunction "4_4") (pintype "passive"))
      (node (ref "J2") (pin "4") (pinfunction "4_4") (pintype "passive"))
    )
    (net (code "75") (name "Net-(J1-Pad5)") (class "Default")
      (node (ref "J1") (pin "5") (pinfunction "5_5") (pintype "passive"))
      (node (ref "J2") (pin "5") (pinfunction "5_5") (pintype "passive"))
    )
    (net (code "76") (name "Net-(J1-Pad6)") (class "Default")
      (node (ref "J1") (pin "6") (pinfunction "6_6") (pintype "passive"))
      (node (ref "J2") (pin "6") (pinfunction "6_6") (pintype "passive"))
    )
    (net (code "77") (name "Net-(J1-Pad8)") (class "Default")
      (node (ref "J1") (pin "8") (pinfunction "8_8") (pintype "passive"))
      (node (ref "J2") (pin "8") (pinfunction "8_8") (pintype "passive"))
    )
    (net (code "78") (name "Net-(RN1B-1)") (class "Default")
      (node (ref "C2") (pin "1") (pinfunction "1_1") (pintype "passive"))
      (node (ref "RN1") (pin "2") (pinfunction "1_2") (pintype "passive"))
      (node (ref "RN2") (pin "3") (pinfunction "3_3") (pintype "passive"))
      (node (ref "X1") (pin "3.1") (pinfunction "1A_3.1") (pintype "passive"))
      (node (ref "X1") (pin "3.2") (pinfunction "1A_3.2") (pintype "passive"))
    )
    (net (code "79") (name "Net-(RN1C-1)") (class "Default")
      (node (ref "C3") (pin "1") (pinfunction "1_1") (pintype "passive"))
      (node (ref "RN1") (pin "3") (pinfunction "1_3") (pintype "passive"))
      (node (ref "RN2") (pin "4") (pinfunction "4_4") (pintype "passive"))
      (node (ref "X1") (pin "4.1") (pinfunction "1A_4.1") (pintype "passive"))
      (node (ref "X1") (pin "4.2") (pinfunction "1A_4.2") (pintype "passive"))
    )
    (net (code "80") (name "Net-(RN1D-1)") (class "Default")
      (node (ref "C4") (pin "1") (pinfunction "1_1") (pintype "passive"))
      (node (ref "RN1") (pin "4") (pinfunction "1_4") (pintype "passive"))
      (node (ref "RN2") (pin "5") (pinfunction "5_5") (pintype "passive"))
      (node (ref "X1") (pin "5.1") (pinfunction "1A_5.1") (pintype "passive"))
      (node (ref "X1") (pin "5.2") (pinfunction "1A_5.2") (pintype "passive"))
    )
    (net (code "81") (name "Net-(RN1E-1)") (class "Default")
      (node (ref "C5") (pin "1") (pinfunction "1_1") (pintype "passive"))
      (node (ref "RN1") (pin "5") (pinfunction "1_5") (pintype "passive"))
      (node (ref "RN2") (pin "6") (pinfunction "6_6") (pintype "passive"))
      (node (ref "X1") (pin "6.1") (pinfunction "1A_6.1") (pintype "passive"))
      (node (ref "X1") (pin "6.2") (pinfunction "1A_6.2") (pintype "passive"))
    )
    (net (code "82") (name "Net-(RN1F-1)") (class "Default")
      (node (ref "C6") (pin "1") (pinfunction "1_1") (pintype "passive"))
      (node (ref "RN1") (pin "6") (pinfunction "1_6") (pintype "passive"))
      (node (ref "RN2") (pin "7") (pinfunction "7_7") (pintype "passive"))
      (node (ref "X1") (pin "7.1") (pinfunction "1A_7.1") (pintype "passive"))
      (node (ref "X1") (pin "7.2") (pinfunction "1A_7.2") (pintype "passive"))
    )
    (net (code "83") (name "Net-(RN1G-1)") (class "Default")
      (node (ref "C7") (pin "1") (pinfunction "1_1") (pintype "passive"))
      (node (ref "RN1") (pin "7") (pinfunction "1_7") (pintype "passive"))
      (node (ref "RN2") (pin "8") (pinfunction "8_8") (pintype "passive"))
      (node (ref "X1") (pin "8.1") (pinfunction "1A_8.1") (pintype "passive"))
      (node (ref "X1") (pin "8.2") (pinfunction "1A_8.2") (pintype "passive"))
    )
    (net (code "84") (name "Net-(RN1H-1)") (class "Default")
      (node (ref "C8") (pin "1") (pinfunction "1_1") (pintype "passive"))
      (node (ref "RN1") (pin "8") (pinfunction "1_8") (pintype "passive"))
      (node (ref "RN2") (pin "9") (pinfunction "9_9") (pintype "passive"))
      (node (ref "X1") (pin "9.1") (pinfunction "1A_9.1") (pintype "passive"))
      (node (ref "X1") (pin "9.2") (pinfunction "1A_9.2") (pintype "passive"))
    )
    (net (code "85") (name "unconnected-(DZ2B-A-Pad10)") (class "Default")
      (node (ref "DZ2") (pin "10") (pinfunction "A_10") (pintype "passive"))
    )
    (net (code "86") (name "unconnected-(DZ2B-C-Pad11)") (class "Default")
      (node (ref "DZ2") (pin "11") (pinfunction "C_11") (pintype "passive"))
    )
    (net (code "87") (name "unconnected-(DZ2H-A-Pad7)") (class "Default")
      (node (ref "DZ2") (pin "7") (pinfunction "A_7") (pintype "passive"))
    )
    (net (code "88") (name "unconnected-(DZ2H-C-Pad14)") (class "Default")
      (node (ref "DZ2") (pin "14") (pinfunction "C_14") (pintype "passive"))
    )
    (net (code "89") (name "unconnected-(DZ2I-A-Pad8)") (class "Default")
      (node (ref "DZ2") (pin "8") (pinfunction "A_8") (pintype "passive"))
    )
    (net (code "90") (name "unconnected-(DZ2I-C-Pad13)") (class "Default")
      (node (ref "DZ2") (pin "13") (pinfunction "C_13") (pintype "passive"))
    )
    (net (code "91") (name "unconnected-(DZ2J-A-Pad9)") (class "Default")
      (node (ref "DZ2") (pin "9") (pinfunction "A_9") (pintype "passive"))
    )
    (net (code "92") (name "unconnected-(DZ2J-C-Pad12)") (class "Default")
      (node (ref "DZ2") (pin "12") (pinfunction "C_12") (pintype "passive"))
    )
    (net (code "93") (name "unconnected-(IC2-CD+-Pad10)") (class "Default")
      (node (ref "IC2") (pin "10") (pinfunction "CD+_10") (pintype "passive"))
    )
    (net (code "94") (name "unconnected-(IC5A-QH*-Pad9)") (class "Default")
      (node (ref "IC5") (pin "9") (pinfunction "QH*_9") (pintype "tri_state"))
    )
    (net (code "95") (name "unconnected-(IC7-RS-Pad8)") (class "Default")
      (node (ref "IC7") (pin "8") (pinfunction "RS_8") (pintype "input"))
    )
    (net (code "96") (name "unconnected-(IC7-VREF-Pad5)") (class "Default")
      (node (ref "IC7") (pin "5") (pinfunction "VREF_5") (pintype "output"))
    )
    (net (code "97") (name "unconnected-(J3-Pad2)") (class "Default")
      (node (ref "J3") (pin "2") (pinfunction "2_2") (pintype "passive"))
    )
    (net (code "98") (name "unconnected-(JP1-Pad1)") (class "Default")
      (node (ref "JP1") (pin "1") (pinfunction "1_1") (pintype "passive"))
    )
    (net (code "99") (name "unconnected-(JP1-Pad3)") (class "Default")
      (node (ref "JP1") (pin "3") (pinfunction "3_3") (pintype "passive"))
    )
    (net (code "100") (name "unconnected-(JP1-Pad5)") (class "Default")
      (node (ref "JP1") (pin "5") (pinfunction "5_5") (pintype "passive"))
    )
    (net (code "101") (name "unconnected-(JP1-Pad6)") (class "Default")
      (node (ref "JP1") (pin "6") (pinfunction "6_6") (pintype "passive"))
    )
    (net (code "102") (name "unconnected-(JP1-Pad7)") (class "Default")
      (node (ref "JP1") (pin "7") (pinfunction "7_7") (pintype "passive"))
    )
    (net (code "103") (name "unconnected-(JP1-Pad8)") (class "Default")
      (node (ref "JP1") (pin "8") (pinfunction "8_8") (pintype "passive"))
    )
    (net (code "104") (name "unconnected-(JP1-Pad10)") (class "Default")
      (node (ref "JP1") (pin "10") (pinfunction "10_10") (pintype "passive"))
    )
    (net (code "105") (name "unconnected-(JP1-Pad12)") (class "Default")
      (node (ref "JP1") (pin "12") (pinfunction "12_12") (pintype "passive"))
    )
    (net (code "106") (name "unconnected-(JP1-Pad14)") (class "Default")
      (node (ref "JP1") (pin "14") (pinfunction "14_14") (pintype "passive"))
    )
    (net (code "107") (name "unconnected-(JP1-Pad16)") (class "Default")
      (node (ref "JP1") (pin "16") (pinfunction "16_16") (pintype "passive"))
    )
    (net (code "108") (name "unconnected-(JP1-Pad17)") (class "Default")
      (node (ref "JP1") (pin "17") (pinfunction "17_17") (pintype "passive"))
    )
    (net (code "109") (name "unconnected-(JP1-Pad18)") (class "Default")
      (node (ref "JP1") (pin "18") (pinfunction "18_18") (pintype "passive"))
    )
    (net (code "110") (name "unconnected-(JP1-Pad19)") (class "Default")
      (node (ref "JP1") (pin "19") (pinfunction "19_19") (pintype "passive"))
    )
    (net (code "111") (name "unconnected-(JP1-Pad20)") (class "Default")
      (node (ref "JP1") (pin "20") (pinfunction "20_20") (pintype "passive"))
    )
    (net (code "112") (name "unconnected-(JP2-Pad1)") (class "Default")
      (node (ref "JP2") (pin "1") (pinfunction "1_1") (pintype "passive"))
    )
    (net (code "113") (name "unconnected-(JP2-Pad3)") (class "Default")
      (node (ref "JP2") (pin "3") (pinfunction "3_3") (pintype "passive"))
    )
    (net (code "114") (name "unconnected-(JP2-Pad4)") (class "Default")
      (node (ref "JP2") (pin "4") (pinfunction "4_4") (pintype "passive"))
    )
    (net (code "115") (name "unconnected-(JP2-Pad5)") (class "Default")
      (node (ref "JP2") (pin "5") (pinfunction "5_5") (pintype "passive"))
    )
    (net (code "116") (name "unconnected-(JP2-Pad7)") (class "Default")
      (node (ref "JP2") (pin "7") (pinfunction "7_7") (pintype "passive"))
    )
    (net (code "117") (name "unconnected-(JP2-Pad8)") (class "Default")
      (node (ref "JP2") (pin "8") (pinfunction "8_8") (pintype "passive"))
    )
    (net (code "118") (name "unconnected-(JP2-Pad9)") (class "Default")
      (node (ref "JP2") (pin "9") (pinfunction "9_9") (pintype "passive"))
    )
    (net (code "119") (name "unconnected-(JP2-Pad10)") (class "Default")
      (node (ref "JP2") (pin "10") (pinfunction "10_10") (pintype "passive"))
    )
    (net (code "120") (name "unconnected-(JP2-Pad11)") (class "Default")
      (node (ref "JP2") (pin "11") (pinfunction "11_11") (pintype "passive"))
    )
    (net (code "121") (name "unconnected-(JP2-Pad13)") (class "Default")
      (node (ref "JP2") (pin "13") (pinfunction "13_13") (pintype "passive"))
    )
    (net (code "122") (name "unconnected-(JP2-Pad15)") (class "Default")
      (node (ref "JP2") (pin "15") (pinfunction "15_15") (pintype "passive"))
    )
    (net (code "123") (name "unconnected-(JP2-Pad17)") (class "Default")
      (node (ref "JP2") (pin "17") (pinfunction "17_17") (pintype "passive"))
    )
    (net (code "124") (name "unconnected-(JP2-Pad19)") (class "Default")
      (node (ref "JP2") (pin "19") (pinfunction "19_19") (pintype "passive"))
    )
    (net (code "125") (name "unconnected-(JP2-Pad20)") (class "Default")
      (node (ref "JP2") (pin "20") (pinfunction "20_20") (pintype "passive"))
    )
    (net (code "126") (name "unconnected-(RN5G-1-Pad7)") (class "Default")
      (node (ref "RN5") (pin "7") (pinfunction "1_7") (pintype "passive"))
    )
    (net (code "127") (name "unconnected-(RN5G-2-Pad8)") (class "Default")
      (node (ref "RN5") (pin "8") (pinfunction "2_8") (pintype "passive"))
    )
  )
)
